# OLED.net
KiCad netlist of a schematic drawn in EAGLE
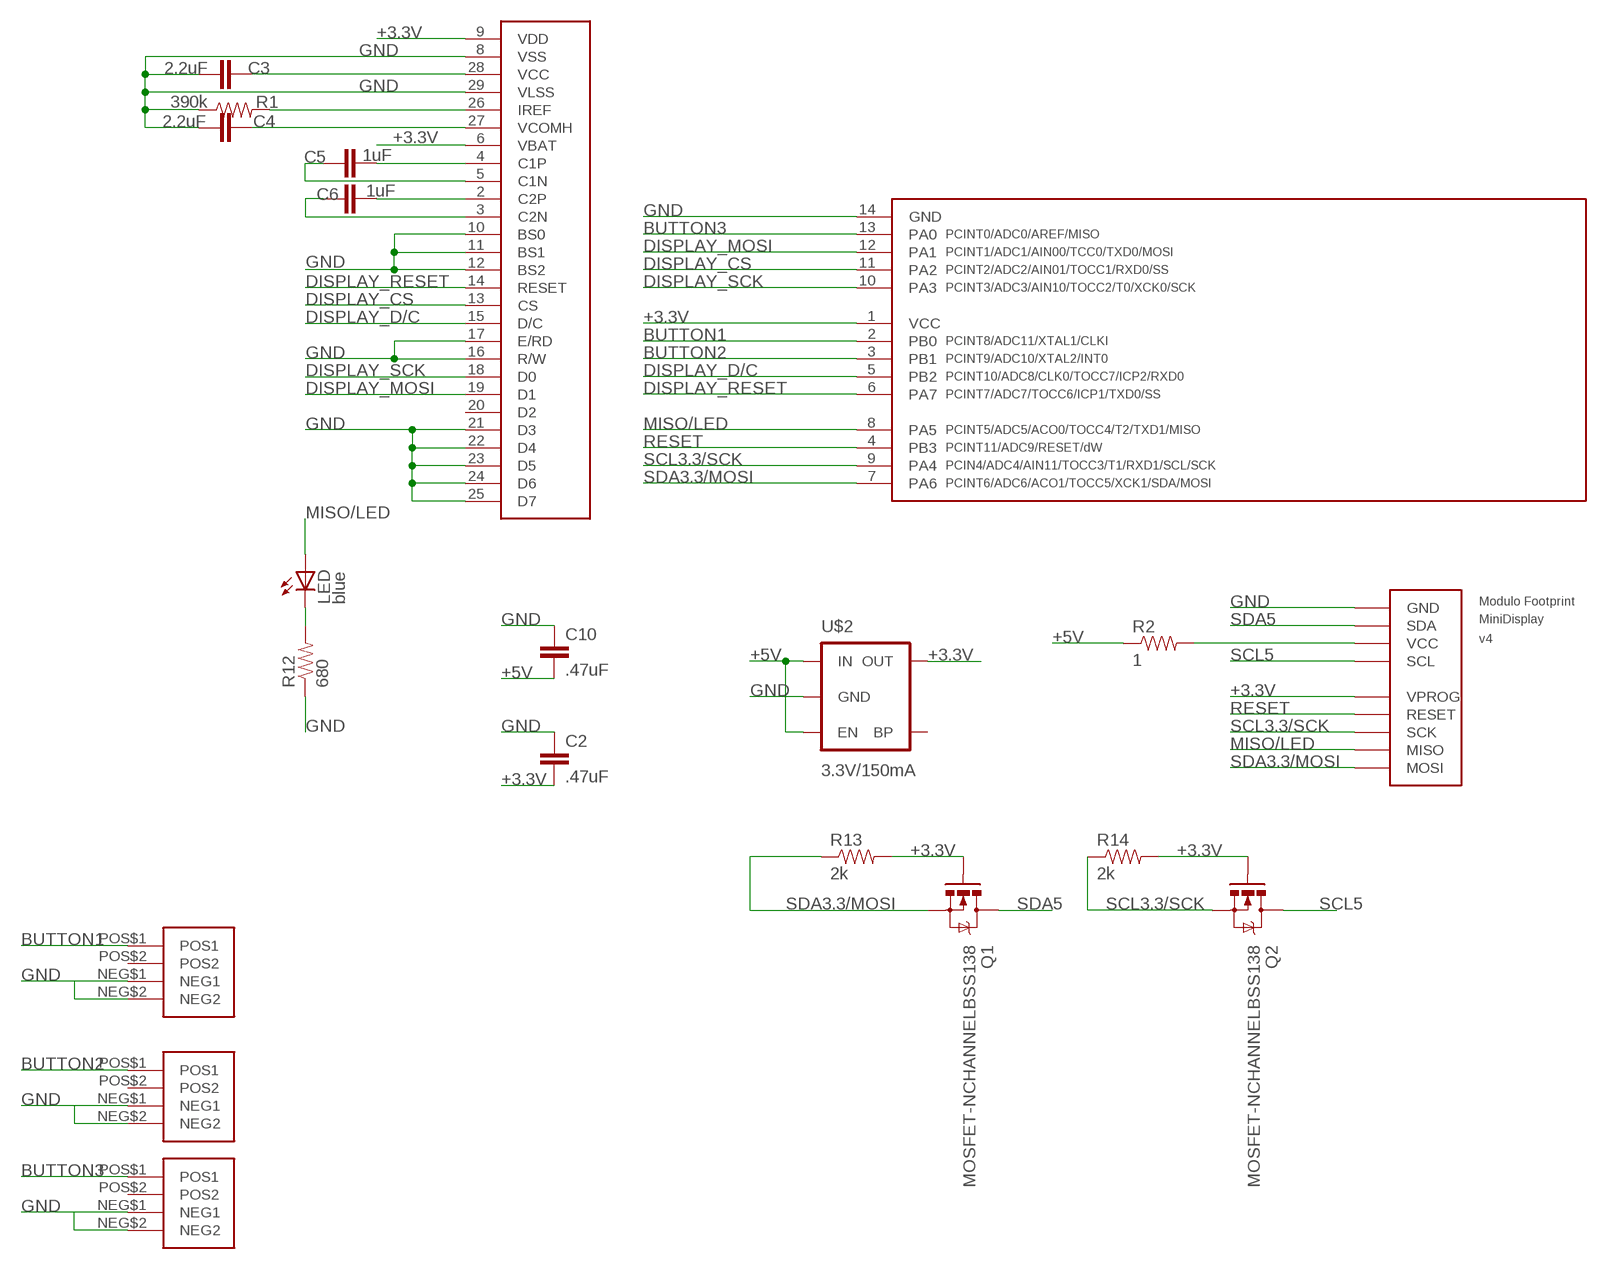
[diagram p0: schematic, sheet 1]

(export (version "E")
  (design (tool "Eeschema 10.0.6"))
  (components
    (comp (ref "C2")
      (value ".47uF")
      (footprint "eagle-import:0805")
      (libsource (lib "eagle-import") (part "CAP0805"))
    )
    (comp (ref "C3")
      (value "2.2uF")
      (footprint "eagle-import:0805")
      (libsource (lib "eagle-import") (part "CAP0805"))
    )
    (comp (ref "C4")
      (value "2.2uF")
      (footprint "eagle-import:0805")
      (libsource (lib "eagle-import") (part "CAP0805"))
    )
    (comp (ref "C5")
      (value "1uF")
      (footprint "eagle-import:0805")
      (libsource (lib "eagle-import") (part "CAP0805"))
    )
    (comp (ref "C6")
      (value "1uF")
      (footprint "eagle-import:0805")
      (libsource (lib "eagle-import") (part "CAP0805"))
    )
    (comp (ref "C10")
      (value ".47uF")
      (footprint "eagle-import:0805")
      (libsource (lib "eagle-import") (part "CAP0805"))
    )
    (comp (ref "LED")
      (value "blue")
      (footprint "eagle-import:CHIP-LED0805")
      (libsource (lib "eagle-import") (part "LEDCHIP-LED0805"))
    )
    (comp (ref "Q1")
      (value "MOSFET-NCHANNELBSS138")
      (footprint "eagle-import:SOT23")
      (libsource (lib "eagle-import") (part "MOSFET-NCHANNELBSS138"))
    )
    (comp (ref "Q2")
      (value "MOSFET-NCHANNELBSS138")
      (footprint "eagle-import:SOT23")
      (libsource (lib "eagle-import") (part "MOSFET-NCHANNELBSS138"))
    )
    (comp (ref "R1")
      (value "390k")
      (footprint "eagle-import:0603-RES")
      (libsource (lib "eagle-import") (part "RESISTOR0603"))
    )
    (comp (ref "R2")
      (value "1")
      (footprint "eagle-import:0805")
      (libsource (lib "eagle-import") (part "RESISTOR0805-RES"))
    )
    (comp (ref "R12")
      (value "680")
      (footprint "eagle-import:0805")
      (libsource (lib "eagle-import") (part "RESISTOR0805-RES"))
    )
    (comp (ref "R13")
      (value "2k")
      (footprint "eagle-import:0805")
      (libsource (lib "eagle-import") (part "RESISTOR0805-RES"))
    )
    (comp (ref "R14")
      (value "2k")
      (footprint "eagle-import:0805")
      (libsource (lib "eagle-import") (part "RESISTOR0805-RES"))
    )
    (comp (ref "U$1")
      (value "OLEDREVERSE")
      (footprint "eagle-import:FPC-30-REVERSE")
      (libsource (lib "eagle-import") (part "OLEDREVERSE"))
    )
    (comp (ref "U$2")
      (value "3.3V/150mA")
      (footprint "eagle-import:SOT23-5")
      (libsource (lib "eagle-import") (part "V_REG_MIC52053.3V"))
    )
    (comp (ref "U$3")
      (value "TINY841")
      (footprint "eagle-import:SOIC14")
      (libsource (lib "eagle-import") (part "TINY841"))
    )
    (comp (ref "U$4")
      (value "FOOTPRINTFOOTPRINT-2")
      (footprint "eagle-import:FOOTPRINT2")
      (fields (field (name "BOARD") "MiniDisplay") (field (name "VERSION") "v4"))
      (libsource (lib "eagle-import") (part "FOOTPRINTFOOTPRINT-2"))
    )
    (comp (ref "U$5")
      (value "TACT-SWITCHBOURNS-7914J")
      (footprint "eagle-import:BOURNS-7914J")
      (libsource (lib "eagle-import") (part "TACT-SWITCHBOURNS-7914J"))
    )
    (comp (ref "U$6")
      (value "TACT-SWITCHBOURNS-7914J")
      (footprint "eagle-import:BOURNS-7914J")
      (libsource (lib "eagle-import") (part "TACT-SWITCHBOURNS-7914J"))
    )
    (comp (ref "U$7")
      (value "TACT-SWITCHBOURNS-7914J")
      (footprint "eagle-import:BOURNS-7914J")
      (libsource (lib "eagle-import") (part "TACT-SWITCHBOURNS-7914J"))
    )
  )
  (nets
    (net (code "1") (name "/+3.3V") (class "Default")
      (node (ref "C2") (pin "2") (pinfunction "2_2") (pintype "passive"))
      (node (ref "Q1") (pin "1") (pinfunction "G_1") (pintype "passive"))
      (node (ref "Q2") (pin "1") (pinfunction "G_1") (pintype "passive"))
      (node (ref "R13") (pin "2") (pinfunction "2_2") (pintype "passive"))
      (node (ref "R14") (pin "2") (pinfunction "2_2") (pintype "passive"))
      (node (ref "U$1") (pin "6") (pinfunction "VBAT_6") (pintype "bidirectional"))
      (node (ref "U$1") (pin "9") (pinfunction "VDD_9") (pintype "bidirectional"))
      (node (ref "U$2") (pin "5") (pinfunction "OUT_5") (pintype "passive"))
      (node (ref "U$3") (pin "1") (pinfunction "VCC_1") (pintype "bidirectional"))
      (node (ref "U$4") (pin "PROG0") (pinfunction "VPROG_PROG0") (pintype "bidirectional"))
    )
    (net (code "2") (name "/+5V") (class "Default")
      (node (ref "C10") (pin "2") (pinfunction "2_2") (pintype "passive"))
      (node (ref "R2") (pin "1") (pinfunction "1_1") (pintype "passive"))
      (node (ref "U$2") (pin "1") (pinfunction "IN_1") (pintype "input"))
      (node (ref "U$2") (pin "3") (pinfunction "EN_3") (pintype "input"))
    )
    (net (code "3") (name "/BUTTON1") (class "Default")
      (node (ref "U$3") (pin "2") (pinfunction "PB0_2") (pintype "bidirectional"))
      (node (ref "U$5") (pin "POS$1") (pinfunction "POS1_POS$1") (pintype "bidirectional"))
    )
    (net (code "4") (name "/BUTTON2") (class "Default")
      (node (ref "U$3") (pin "3") (pinfunction "PB1_3") (pintype "bidirectional"))
      (node (ref "U$6") (pin "POS$1") (pinfunction "POS1_POS$1") (pintype "bidirectional"))
    )
    (net (code "5") (name "/BUTTON3") (class "Default")
      (node (ref "U$3") (pin "13") (pinfunction "PA0_13") (pintype "bidirectional"))
      (node (ref "U$7") (pin "POS$1") (pinfunction "POS1_POS$1") (pintype "bidirectional"))
    )
    (net (code "6") (name "/DISPLAY_CS") (class "Default")
      (node (ref "U$1") (pin "13") (pinfunction "CS_13") (pintype "bidirectional"))
      (node (ref "U$3") (pin "11") (pinfunction "PA2_11") (pintype "bidirectional"))
    )
    (net (code "7") (name "/DISPLAY_D{slash}C") (class "Default")
      (node (ref "U$1") (pin "15") (pinfunction "D/C_15") (pintype "bidirectional"))
      (node (ref "U$3") (pin "5") (pinfunction "PB2_5") (pintype "bidirectional"))
    )
    (net (code "8") (name "/DISPLAY_MOSI") (class "Default")
      (node (ref "U$1") (pin "19") (pinfunction "D1_19") (pintype "bidirectional"))
      (node (ref "U$3") (pin "12") (pinfunction "PA1_12") (pintype "bidirectional"))
    )
    (net (code "9") (name "/DISPLAY_RESET") (class "Default")
      (node (ref "U$1") (pin "14") (pinfunction "RESET_14") (pintype "bidirectional"))
      (node (ref "U$3") (pin "6") (pinfunction "PA7_6") (pintype "bidirectional"))
    )
    (net (code "10") (name "/DISPLAY_SCK") (class "Default")
      (node (ref "U$1") (pin "18") (pinfunction "D0_18") (pintype "bidirectional"))
      (node (ref "U$3") (pin "10") (pinfunction "PA3_10") (pintype "bidirectional"))
    )
    (net (code "11") (name "/GND") (class "Default")
      (node (ref "C10") (pin "1") (pinfunction "1_1") (pintype "passive"))
      (node (ref "C2") (pin "1") (pinfunction "1_1") (pintype "passive"))
      (node (ref "C3") (pin "2") (pinfunction "2_2") (pintype "passive"))
      (node (ref "C4") (pin "2") (pinfunction "2_2") (pintype "passive"))
      (node (ref "R1") (pin "1") (pinfunction "1_1") (pintype "passive"))
      (node (ref "R12") (pin "1") (pinfunction "1_1") (pintype "passive"))
      (node (ref "U$1") (pin "10") (pinfunction "BS0_10") (pintype "bidirectional"))
      (node (ref "U$1") (pin "11") (pinfunction "BS1_11") (pintype "bidirectional"))
      (node (ref "U$1") (pin "12") (pinfunction "BS2_12") (pintype "bidirectional"))
      (node (ref "U$1") (pin "16") (pinfunction "R/W_16") (pintype "bidirectional"))
      (node (ref "U$1") (pin "17") (pinfunction "E/RD_17") (pintype "bidirectional"))
      (node (ref "U$1") (pin "21") (pinfunction "D3_21") (pintype "bidirectional"))
      (node (ref "U$1") (pin "22") (pinfunction "D4_22") (pintype "bidirectional"))
      (node (ref "U$1") (pin "23") (pinfunction "D5_23") (pintype "bidirectional"))
      (node (ref "U$1") (pin "24") (pinfunction "D6_24") (pintype "bidirectional"))
      (node (ref "U$1") (pin "25") (pinfunction "D7_25") (pintype "bidirectional"))
      (node (ref "U$1") (pin "29") (pinfunction "VLSS_29") (pintype "bidirectional"))
      (node (ref "U$1") (pin "8") (pinfunction "VSS_8") (pintype "bidirectional"))
      (node (ref "U$2") (pin "2") (pinfunction "GND_2") (pintype "input"))
      (node (ref "U$3") (pin "14") (pinfunction "GND_14") (pintype "bidirectional"))
      (node (ref "U$4") (pin "BUS0") (pinfunction "GND_BUS0") (pintype "bidirectional"))
      (node (ref "U$5") (pin "NEG$1") (pinfunction "NEG1_NEG$1") (pintype "bidirectional"))
      (node (ref "U$5") (pin "NEG$2") (pinfunction "NEG2_NEG$2") (pintype "bidirectional"))
      (node (ref "U$6") (pin "NEG$1") (pinfunction "NEG1_NEG$1") (pintype "bidirectional"))
      (node (ref "U$6") (pin "NEG$2") (pinfunction "NEG2_NEG$2") (pintype "bidirectional"))
      (node (ref "U$7") (pin "NEG$1") (pinfunction "NEG1_NEG$1") (pintype "bidirectional"))
      (node (ref "U$7") (pin "NEG$2") (pinfunction "NEG2_NEG$2") (pintype "bidirectional"))
    )
    (net (code "12") (name "/MISO{slash}LED") (class "Default")
      (node (ref "LED") (pin "A") (pinfunction "A_A") (pintype "passive"))
      (node (ref "U$3") (pin "8") (pinfunction "PA5_8") (pintype "bidirectional"))
      (node (ref "U$4") (pin "PROG3") (pinfunction "MISO_PROG3") (pintype "bidirectional"))
    )
    (net (code "13") (name "/RESET") (class "Default")
      (node (ref "U$3") (pin "4") (pinfunction "PB3_4") (pintype "bidirectional"))
      (node (ref "U$4") (pin "PROG1") (pinfunction "RESET_PROG1") (pintype "bidirectional"))
    )
    (net (code "14") (name "/SCL3.3{slash}SCK") (class "Default")
      (node (ref "Q2") (pin "2") (pinfunction "S_2") (pintype "passive"))
      (node (ref "R14") (pin "1") (pinfunction "1_1") (pintype "passive"))
      (node (ref "U$3") (pin "9") (pinfunction "PA4_9") (pintype "bidirectional"))
      (node (ref "U$4") (pin "PROG2") (pinfunction "SCK_PROG2") (pintype "bidirectional"))
    )
    (net (code "15") (name "/SCL5") (class "Default")
      (node (ref "Q2") (pin "3") (pinfunction "D_3") (pintype "passive"))
      (node (ref "U$4") (pin "BUS3") (pinfunction "SCL_BUS3") (pintype "bidirectional"))
    )
    (net (code "16") (name "/SDA3.3{slash}MOSI") (class "Default")
      (node (ref "Q1") (pin "2") (pinfunction "S_2") (pintype "passive"))
      (node (ref "R13") (pin "1") (pinfunction "1_1") (pintype "passive"))
      (node (ref "U$3") (pin "7") (pinfunction "PA6_7") (pintype "bidirectional"))
      (node (ref "U$4") (pin "PROG4") (pinfunction "MOSI_PROG4") (pintype "bidirectional"))
    )
    (net (code "17") (name "/SDA5") (class "Default")
      (node (ref "Q1") (pin "3") (pinfunction "D_3") (pintype "passive"))
      (node (ref "U$4") (pin "BUS1") (pinfunction "SDA_BUS1") (pintype "bidirectional"))
    )
    (net (code "18") (name "Net-(LED-PadC)") (class "Default")
      (node (ref "LED") (pin "C") (pinfunction "C_C") (pintype "passive"))
      (node (ref "R12") (pin "2") (pinfunction "2_2") (pintype "passive"))
    )
    (net (code "19") (name "Net-(U$1-C1N)") (class "Default")
      (node (ref "C5") (pin "1") (pinfunction "1_1") (pintype "passive"))
      (node (ref "U$1") (pin "5") (pinfunction "C1N_5") (pintype "bidirectional"))
    )
    (net (code "20") (name "Net-(U$1-C1P)") (class "Default")
      (node (ref "C5") (pin "2") (pinfunction "2_2") (pintype "passive"))
      (node (ref "U$1") (pin "4") (pinfunction "C1P_4") (pintype "bidirectional"))
    )
    (net (code "21") (name "Net-(U$1-C2N)") (class "Default")
      (node (ref "C6") (pin "1") (pinfunction "1_1") (pintype "passive"))
      (node (ref "U$1") (pin "3") (pinfunction "C2N_3") (pintype "bidirectional"))
    )
    (net (code "22") (name "Net-(U$1-C2P)") (class "Default")
      (node (ref "C6") (pin "2") (pinfunction "2_2") (pintype "passive"))
      (node (ref "U$1") (pin "2") (pinfunction "C2P_2") (pintype "bidirectional"))
    )
    (net (code "23") (name "Net-(U$1-IREF)") (class "Default")
      (node (ref "R1") (pin "2") (pinfunction "2_2") (pintype "passive"))
      (node (ref "U$1") (pin "26") (pinfunction "IREF_26") (pintype "bidirectional"))
    )
    (net (code "24") (name "Net-(U$1-VCC)") (class "Default")
      (node (ref "C3") (pin "1") (pinfunction "1_1") (pintype "passive"))
      (node (ref "U$1") (pin "28") (pinfunction "VCC_28") (pintype "bidirectional"))
    )
    (net (code "25") (name "Net-(U$1-VCOMH)") (class "Default")
      (node (ref "C4") (pin "1") (pinfunction "1_1") (pintype "passive"))
      (node (ref "U$1") (pin "27") (pinfunction "VCOMH_27") (pintype "bidirectional"))
    )
    (net (code "26") (name "Net-(U$4-VCC)") (class "Default")
      (node (ref "R2") (pin "2") (pinfunction "2_2") (pintype "passive"))
      (node (ref "U$4") (pin "BUS2") (pinfunction "VCC_BUS2") (pintype "bidirectional"))
    )
    (net (code "27") (name "unconnected-(U$1-D2-Pad20)") (class "Default")
      (node (ref "U$1") (pin "20") (pinfunction "D2_20") (pintype "bidirectional"))
    )
    (net (code "28") (name "unconnected-(U$2-BP-Pad4)") (class "Default")
      (node (ref "U$2") (pin "4") (pinfunction "BP_4") (pintype "input"))
    )
    (net (code "29") (name "unconnected-(U$5-POS2-PadPOS$2)") (class "Default")
      (node (ref "U$5") (pin "POS$2") (pinfunction "POS2_POS$2") (pintype "bidirectional"))
    )
    (net (code "30") (name "unconnected-(U$6-POS2-PadPOS$2)") (class "Default")
      (node (ref "U$6") (pin "POS$2") (pinfunction "POS2_POS$2") (pintype "bidirectional"))
    )
    (net (code "31") (name "unconnected-(U$7-POS2-PadPOS$2)") (class "Default")
      (node (ref "U$7") (pin "POS$2") (pinfunction "POS2_POS$2") (pintype "bidirectional"))
    )
  )
)
